# uav_controller.net
KiCad netlist of a schematic drawn in EAGLE
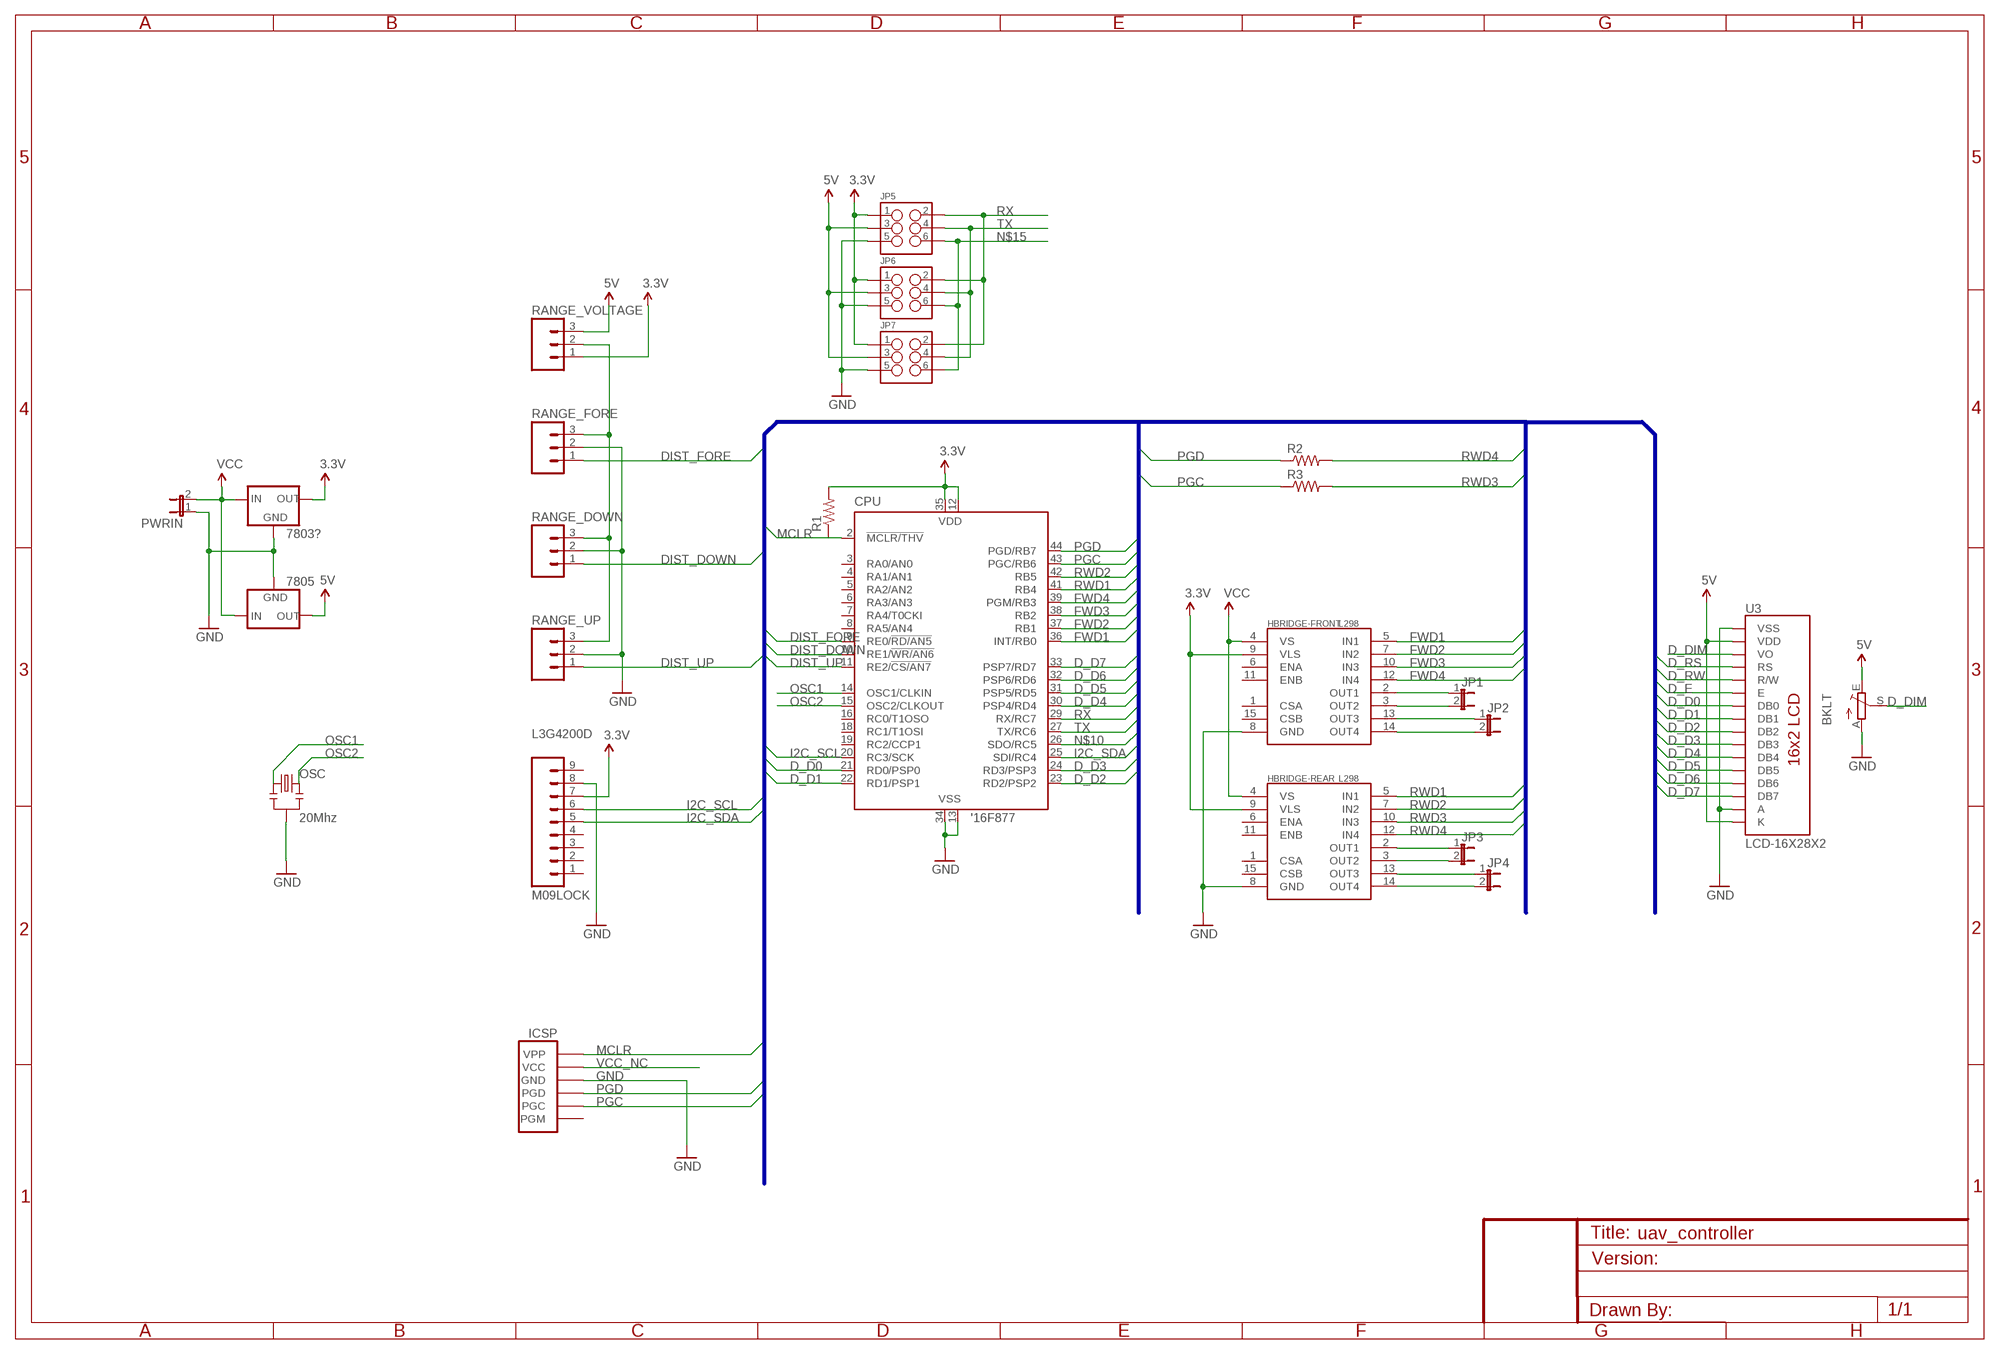
[diagram p0: schematic, sheet 1]

(export (version "E")
  (design (tool "Eeschema 10.0.6"))
  (components
    (comp (ref "7803?")
      (value "V_REG_78XX-TO-220")
      (footprint "eagle-import:TO-220-ALT")
      (libsource (lib "eagle-import") (part "V_REG_78XX-TO-220"))
    )
    (comp (ref "7805")
      (value "V_REG_78XX-TO-220")
      (footprint "eagle-import:TO-220-ALT")
      (libsource (lib "eagle-import") (part "V_REG_78XX-TO-220"))
    )
    (comp (ref "BKLT")
      (value "TRIM_EU-PT10")
      (footprint "eagle-import:PT-10")
      (libsource (lib "eagle-import") (part "TRIM_EU-PT10"))
    )
    (comp (ref "CPU")
      (value "'16F877")
      (footprint "eagle-import:S44")
      (libsource (lib "eagle-import") (part "PIC16F87SO7"))
    )
    (comp (ref "HBRIDGE-FRONT")
      (value "L298")
      (footprint "eagle-import:MULTIWATT15")
      (libsource (lib "eagle-import") (part "L298"))
    )
    (comp (ref "HBRIDGE-REAR")
      (value "L298")
      (footprint "eagle-import:MULTIWATT15")
      (libsource (lib "eagle-import") (part "L298"))
    )
    (comp (ref "ICSP")
      (value "PIC-ICSPPOLAR_LOCK")
      (footprint "eagle-import:MOLEX-1X6_LOCK")
      (libsource (lib "eagle-import") (part "PIC-ICSPPOLAR_LOCK"))
    )
    (comp (ref "JP1")
      (value "JUMPER-2PTH")
      (footprint "eagle-import:1X02")
      (libsource (lib "eagle-import") (part "JUMPER-2PTH"))
    )
    (comp (ref "JP2")
      (value "JUMPER-2PTH")
      (footprint "eagle-import:1X02")
      (libsource (lib "eagle-import") (part "JUMPER-2PTH"))
    )
    (comp (ref "JP3")
      (value "JUMPER-2PTH")
      (footprint "eagle-import:1X02")
      (libsource (lib "eagle-import") (part "JUMPER-2PTH"))
    )
    (comp (ref "JP4")
      (value "JUMPER-2PTH")
      (footprint "eagle-import:1X02")
      (libsource (lib "eagle-import") (part "JUMPER-2PTH"))
    )
    (comp (ref "JP5")
      (value "M03X2")
      (footprint "eagle-import:2X3-SHROUDED")
      (libsource (lib "eagle-import") (part "M03X2"))
    )
    (comp (ref "JP6")
      (value "M03X2")
      (footprint "eagle-import:2X3-SHROUDED")
      (libsource (lib "eagle-import") (part "M03X2"))
    )
    (comp (ref "JP7")
      (value "M03X2")
      (footprint "eagle-import:2X3-SHROUDED")
      (libsource (lib "eagle-import") (part "M03X2"))
    )
    (comp (ref "L3G4200D")
      (value "M09LOCK")
      (footprint "eagle-import:1X09_LOCK")
      (libsource (lib "eagle-import") (part "M09LOCK"))
    )
    (comp (ref "OSC")
      (value "20Mhz")
      (footprint "eagle-import:RESONATOR-PTH")
      (libsource (lib "eagle-import") (part "RESONATORPTH"))
    )
    (comp (ref "PWRIN")
      (value "JUMPER-2PTH")
      (footprint "eagle-import:1X02")
      (libsource (lib "eagle-import") (part "JUMPER-2PTH"))
    )
    (comp (ref "R1")
      (value "RESISTOREZ")
      (footprint "eagle-import:AXIAL-0.3EZ")
      (libsource (lib "eagle-import") (part "RESISTOREZ"))
    )
    (comp (ref "R2")
      (value "RESISTORKIT")
      (footprint "eagle-import:AXIAL-0.3-KIT")
      (libsource (lib "eagle-import") (part "RESISTORKIT"))
    )
    (comp (ref "R3")
      (value "RESISTORKIT")
      (footprint "eagle-import:AXIAL-0.3-KIT")
      (libsource (lib "eagle-import") (part "RESISTORKIT"))
    )
    (comp (ref "RANGE_DOWN")
      (value "M03JST-PTH")
      (footprint "eagle-import:JST-3-PTH")
      (libsource (lib "eagle-import") (part "M03JST-PTH"))
    )
    (comp (ref "RANGE_FORE")
      (value "M03JST-PTH")
      (footprint "eagle-import:JST-3-PTH")
      (libsource (lib "eagle-import") (part "M03JST-PTH"))
    )
    (comp (ref "RANGE_UP")
      (value "M03JST-PTH")
      (footprint "eagle-import:JST-3-PTH")
      (libsource (lib "eagle-import") (part "M03JST-PTH"))
    )
    (comp (ref "RANGE_VOLTAGE")
      (value "M03PTH")
      (footprint "eagle-import:1X03")
      (libsource (lib "eagle-import") (part "M03PTH"))
    )
    (comp (ref "U3")
      (value "LCD-16X28X2")
      (footprint "eagle-import:LCD-8X2")
      (libsource (lib "eagle-import") (part "LCD-16X28X2"))
    )
  )
  (nets
    (net (code "1") (name "/DIST_DOWN") (class "Default")
      (node (ref "CPU") (pin "10") (pinfunction "RE1/~{WR/AN6}_10") (pintype "bidirectional"))
      (node (ref "RANGE_DOWN") (pin "1") (pinfunction "1_1") (pintype "passive"))
    )
    (net (code "2") (name "/DIST_FORE") (class "Default")
      (node (ref "CPU") (pin "9") (pinfunction "RE0/~{RD/AN5}_9") (pintype "bidirectional"))
      (node (ref "RANGE_FORE") (pin "1") (pinfunction "1_1") (pintype "passive"))
    )
    (net (code "3") (name "/DIST_UP") (class "Default")
      (node (ref "CPU") (pin "11") (pinfunction "RE2/~{CS/AN7}_11") (pintype "bidirectional"))
      (node (ref "RANGE_UP") (pin "1") (pinfunction "1_1") (pintype "passive"))
    )
    (net (code "4") (name "/D_D0") (class "Default")
      (node (ref "CPU") (pin "21") (pinfunction "RD0/PSP0_21") (pintype "bidirectional"))
      (node (ref "U3") (pin "7") (pinfunction "DB0_7") (pintype "bidirectional"))
    )
    (net (code "5") (name "/D_D1") (class "Default")
      (node (ref "CPU") (pin "22") (pinfunction "RD1/PSP1_22") (pintype "bidirectional"))
      (node (ref "U3") (pin "8") (pinfunction "DB1_8") (pintype "bidirectional"))
    )
    (net (code "6") (name "/D_D2") (class "Default")
      (node (ref "CPU") (pin "23") (pinfunction "RD2/PSP2_23") (pintype "bidirectional"))
      (node (ref "U3") (pin "9") (pinfunction "DB2_9") (pintype "bidirectional"))
    )
    (net (code "7") (name "/D_D3") (class "Default")
      (node (ref "CPU") (pin "24") (pinfunction "RD3/PSP3_24") (pintype "bidirectional"))
      (node (ref "U3") (pin "10") (pinfunction "DB3_10") (pintype "bidirectional"))
    )
    (net (code "8") (name "/D_D4") (class "Default")
      (node (ref "CPU") (pin "30") (pinfunction "PSP4/RD4_30") (pintype "bidirectional"))
      (node (ref "U3") (pin "11") (pinfunction "DB4_11") (pintype "bidirectional"))
    )
    (net (code "9") (name "/D_D5") (class "Default")
      (node (ref "CPU") (pin "31") (pinfunction "PSP5/RD5_31") (pintype "bidirectional"))
      (node (ref "U3") (pin "12") (pinfunction "DB5_12") (pintype "bidirectional"))
    )
    (net (code "10") (name "/D_D6") (class "Default")
      (node (ref "CPU") (pin "32") (pinfunction "PSP6/RD6_32") (pintype "bidirectional"))
      (node (ref "U3") (pin "13") (pinfunction "DB6_13") (pintype "bidirectional"))
    )
    (net (code "11") (name "/D_D7") (class "Default")
      (node (ref "CPU") (pin "33") (pinfunction "PSP7/RD7_33") (pintype "bidirectional"))
      (node (ref "U3") (pin "14") (pinfunction "DB7_14") (pintype "bidirectional"))
    )
    (net (code "12") (name "/D_DIM") (class "Default")
      (node (ref "BKLT") (pin "S") (pinfunction "S_S") (pintype "passive"))
      (node (ref "U3") (pin "3") (pinfunction "VO_3") (pintype "bidirectional"))
    )
    (net (code "13") (name "/D_E") (class "Default")
      (node (ref "U3") (pin "6") (pinfunction "E_6") (pintype "input"))
    )
    (net (code "14") (name "/D_RS") (class "Default")
      (node (ref "U3") (pin "4") (pinfunction "RS_4") (pintype "input"))
    )
    (net (code "15") (name "/D_RW") (class "Default")
      (node (ref "U3") (pin "5") (pinfunction "R/W_5") (pintype "input"))
    )
    (net (code "16") (name "/FWD1") (class "Default")
      (node (ref "CPU") (pin "36") (pinfunction "INT/RB0_36") (pintype "bidirectional"))
      (node (ref "HBRIDGE-FRONT") (pin "5") (pinfunction "IN1_5") (pintype "bidirectional"))
    )
    (net (code "17") (name "/FWD2") (class "Default")
      (node (ref "CPU") (pin "37") (pinfunction "RB1_37") (pintype "bidirectional"))
      (node (ref "HBRIDGE-FRONT") (pin "7") (pinfunction "IN2_7") (pintype "bidirectional"))
    )
    (net (code "18") (name "/FWD3") (class "Default")
      (node (ref "CPU") (pin "38") (pinfunction "RB2_38") (pintype "bidirectional"))
      (node (ref "HBRIDGE-FRONT") (pin "10") (pinfunction "IN3_10") (pintype "bidirectional"))
    )
    (net (code "19") (name "/FWD4") (class "Default")
      (node (ref "CPU") (pin "39") (pinfunction "PGM/RB3_39") (pintype "bidirectional"))
      (node (ref "HBRIDGE-FRONT") (pin "12") (pinfunction "IN4_12") (pintype "bidirectional"))
    )
    (net (code "20") (name "/I2C_SCL") (class "Default")
      (node (ref "CPU") (pin "20") (pinfunction "RC3/SCK_20") (pintype "bidirectional"))
      (node (ref "L3G4200D") (pin "6") (pinfunction "6_6") (pintype "passive"))
    )
    (net (code "21") (name "/I2C_SDA") (class "Default")
      (node (ref "CPU") (pin "25") (pinfunction "SDI/RC4_25") (pintype "bidirectional"))
      (node (ref "L3G4200D") (pin "5") (pinfunction "5_5") (pintype "passive"))
    )
    (net (code "22") (name "/MCLR") (class "Default")
      (node (ref "CPU") (pin "2") (pinfunction "~{MCLR/THV}_2") (pintype "input"))
      (node (ref "ICSP") (pin "6") (pinfunction "VPP_6") (pintype "bidirectional"))
      (node (ref "R1") (pin "P$1") (pinfunction "1_P$1") (pintype "passive"))
    )
    (net (code "23") (name "/N$10") (class "Default")
      (node (ref "CPU") (pin "26") (pinfunction "SDO/RC5_26") (pintype "bidirectional"))
    )
    (net (code "24") (name "/N$15") (class "Default")
      (node (ref "JP5") (pin "6") (pinfunction "6_6") (pintype "bidirectional"))
      (node (ref "JP6") (pin "6") (pinfunction "6_6") (pintype "bidirectional"))
      (node (ref "JP7") (pin "6") (pinfunction "6_6") (pintype "bidirectional"))
    )
    (net (code "25") (name "/OSC1") (class "Default")
      (node (ref "CPU") (pin "14") (pinfunction "OSC1/CLKIN_14") (pintype "input"))
      (node (ref "OSC") (pin "1") (pinfunction "1_1") (pintype "passive"))
    )
    (net (code "26") (name "/OSC2") (class "Default")
      (node (ref "CPU") (pin "15") (pinfunction "OSC2/CLKOUT_15") (pintype "output"))
      (node (ref "OSC") (pin "3") (pinfunction "3_3") (pintype "passive"))
    )
    (net (code "27") (name "/PGC") (class "Default")
      (node (ref "CPU") (pin "43") (pinfunction "PGC/RB6_43") (pintype "bidirectional"))
      (node (ref "ICSP") (pin "2") (pinfunction "PGC_2") (pintype "bidirectional"))
      (node (ref "R3") (pin "P$1") (pinfunction "1_P$1") (pintype "passive"))
    )
    (net (code "28") (name "/PGD") (class "Default")
      (node (ref "CPU") (pin "44") (pinfunction "PGD/RB7_44") (pintype "bidirectional"))
      (node (ref "ICSP") (pin "3") (pinfunction "PGD_3") (pintype "bidirectional"))
      (node (ref "R2") (pin "P$1") (pinfunction "1_P$1") (pintype "passive"))
    )
    (net (code "29") (name "/RWD1") (class "Default")
      (node (ref "CPU") (pin "41") (pinfunction "RB4_41") (pintype "bidirectional"))
      (node (ref "HBRIDGE-REAR") (pin "5") (pinfunction "IN1_5") (pintype "bidirectional"))
    )
    (net (code "30") (name "/RWD2") (class "Default")
      (node (ref "CPU") (pin "42") (pinfunction "RB5_42") (pintype "bidirectional"))
      (node (ref "HBRIDGE-REAR") (pin "7") (pinfunction "IN2_7") (pintype "bidirectional"))
    )
    (net (code "31") (name "/RWD3") (class "Default")
      (node (ref "HBRIDGE-REAR") (pin "10") (pinfunction "IN3_10") (pintype "bidirectional"))
      (node (ref "R3") (pin "P$2") (pinfunction "2_P$2") (pintype "passive"))
    )
    (net (code "32") (name "/RWD4") (class "Default")
      (node (ref "HBRIDGE-REAR") (pin "12") (pinfunction "IN4_12") (pintype "bidirectional"))
      (node (ref "R2") (pin "P$2") (pinfunction "2_P$2") (pintype "passive"))
    )
    (net (code "33") (name "/RX") (class "Default")
      (node (ref "CPU") (pin "29") (pinfunction "RX/RC7_29") (pintype "bidirectional"))
      (node (ref "JP5") (pin "2") (pinfunction "2_2") (pintype "bidirectional"))
      (node (ref "JP6") (pin "2") (pinfunction "2_2") (pintype "bidirectional"))
      (node (ref "JP7") (pin "2") (pinfunction "2_2") (pintype "bidirectional"))
    )
    (net (code "34") (name "/TX") (class "Default")
      (node (ref "CPU") (pin "27") (pinfunction "TX/RC6_27") (pintype "bidirectional"))
      (node (ref "JP5") (pin "4") (pinfunction "4_4") (pintype "bidirectional"))
      (node (ref "JP6") (pin "4") (pinfunction "4_4") (pintype "bidirectional"))
      (node (ref "JP7") (pin "4") (pinfunction "4_4") (pintype "bidirectional"))
    )
    (net (code "35") (name "/VCC_NC") (class "Default")
      (node (ref "ICSP") (pin "5") (pinfunction "VCC_5") (pintype "bidirectional"))
    )
    (net (code "36") (name "3.3V") (class "Default")
      (node (ref "7803?") (pin "OUT") (pinfunction "OUT_OUT") (pintype "output"))
      (node (ref "CPU") (pin "12") (pinfunction "VDD_12") (pintype "power_in"))
      (node (ref "CPU") (pin "35") (pinfunction "VDD_35") (pintype "power_in"))
      (node (ref "HBRIDGE-FRONT") (pin "9") (pinfunction "VLS_9") (pintype "bidirectional"))
      (node (ref "HBRIDGE-REAR") (pin "9") (pinfunction "VLS_9") (pintype "bidirectional"))
      (node (ref "JP5") (pin "1") (pinfunction "1_1") (pintype "bidirectional"))
      (node (ref "JP6") (pin "1") (pinfunction "1_1") (pintype "bidirectional"))
      (node (ref "JP7") (pin "1") (pinfunction "1_1") (pintype "bidirectional"))
      (node (ref "L3G4200D") (pin "7") (pinfunction "7_7") (pintype "passive"))
      (node (ref "R1") (pin "P$2") (pinfunction "2_P$2") (pintype "passive"))
      (node (ref "RANGE_VOLTAGE") (pin "1") (pinfunction "1_1") (pintype "passive"))
    )
    (net (code "37") (name "5V") (class "Default")
      (node (ref "7805") (pin "OUT") (pinfunction "OUT_OUT") (pintype "output"))
      (node (ref "BKLT") (pin "E") (pinfunction "E_E") (pintype "passive"))
      (node (ref "JP5") (pin "3") (pinfunction "3_3") (pintype "bidirectional"))
      (node (ref "JP6") (pin "3") (pinfunction "3_3") (pintype "bidirectional"))
      (node (ref "JP7") (pin "3") (pinfunction "3_3") (pintype "bidirectional"))
      (node (ref "RANGE_VOLTAGE") (pin "3") (pinfunction "3_3") (pintype "passive"))
      (node (ref "U3") (pin "16") (pinfunction "K_16") (pintype "power_in"))
      (node (ref "U3") (pin "2") (pinfunction "VDD_2") (pintype "power_in"))
    )
    (net (code "38") (name "GND") (class "Default")
      (node (ref "7803?") (pin "GND") (pinfunction "GND_GND") (pintype "input"))
      (node (ref "7805") (pin "GND") (pinfunction "GND_GND") (pintype "input"))
      (node (ref "BKLT") (pin "A") (pinfunction "A_A") (pintype "passive"))
      (node (ref "CPU") (pin "13") (pinfunction "VSS_13") (pintype "power_in"))
      (node (ref "CPU") (pin "34") (pinfunction "VSS_34") (pintype "power_in"))
      (node (ref "HBRIDGE-FRONT") (pin "8") (pinfunction "GND_8") (pintype "bidirectional"))
      (node (ref "HBRIDGE-REAR") (pin "8") (pinfunction "GND_8") (pintype "bidirectional"))
      (node (ref "ICSP") (pin "4") (pinfunction "GND_4") (pintype "bidirectional"))
      (node (ref "JP5") (pin "5") (pinfunction "5_5") (pintype "bidirectional"))
      (node (ref "JP6") (pin "5") (pinfunction "5_5") (pintype "bidirectional"))
      (node (ref "JP7") (pin "5") (pinfunction "5_5") (pintype "bidirectional"))
      (node (ref "L3G4200D") (pin "8") (pinfunction "8_8") (pintype "passive"))
      (node (ref "OSC") (pin "2") (pinfunction "2_2") (pintype "passive"))
      (node (ref "PWRIN") (pin "1") (pinfunction "1_1") (pintype "passive"))
      (node (ref "RANGE_DOWN") (pin "2") (pinfunction "2_2") (pintype "passive"))
      (node (ref "RANGE_FORE") (pin "2") (pinfunction "2_2") (pintype "passive"))
      (node (ref "RANGE_UP") (pin "2") (pinfunction "2_2") (pintype "passive"))
      (node (ref "U3") (pin "1") (pinfunction "VSS_1") (pintype "power_in"))
      (node (ref "U3") (pin "15") (pinfunction "A_15") (pintype "power_in"))
    )
    (net (code "39") (name "Net-(HBRIDGE-FRONT-OUT1)") (class "Default")
      (node (ref "HBRIDGE-FRONT") (pin "2") (pinfunction "OUT1_2") (pintype "bidirectional"))
      (node (ref "JP1") (pin "1") (pinfunction "1_1") (pintype "passive"))
    )
    (net (code "40") (name "Net-(HBRIDGE-FRONT-OUT2)") (class "Default")
      (node (ref "HBRIDGE-FRONT") (pin "3") (pinfunction "OUT2_3") (pintype "bidirectional"))
      (node (ref "JP1") (pin "2") (pinfunction "2_2") (pintype "passive"))
    )
    (net (code "41") (name "Net-(HBRIDGE-FRONT-OUT3)") (class "Default")
      (node (ref "HBRIDGE-FRONT") (pin "13") (pinfunction "OUT3_13") (pintype "bidirectional"))
      (node (ref "JP2") (pin "1") (pinfunction "1_1") (pintype "passive"))
    )
    (net (code "42") (name "Net-(HBRIDGE-FRONT-OUT4)") (class "Default")
      (node (ref "HBRIDGE-FRONT") (pin "14") (pinfunction "OUT4_14") (pintype "bidirectional"))
      (node (ref "JP2") (pin "2") (pinfunction "2_2") (pintype "passive"))
    )
    (net (code "43") (name "Net-(HBRIDGE-REAR-OUT1)") (class "Default")
      (node (ref "HBRIDGE-REAR") (pin "2") (pinfunction "OUT1_2") (pintype "bidirectional"))
      (node (ref "JP3") (pin "1") (pinfunction "1_1") (pintype "passive"))
    )
    (net (code "44") (name "Net-(HBRIDGE-REAR-OUT2)") (class "Default")
      (node (ref "HBRIDGE-REAR") (pin "3") (pinfunction "OUT2_3") (pintype "bidirectional"))
      (node (ref "JP3") (pin "2") (pinfunction "2_2") (pintype "passive"))
    )
    (net (code "45") (name "Net-(HBRIDGE-REAR-OUT3)") (class "Default")
      (node (ref "HBRIDGE-REAR") (pin "13") (pinfunction "OUT3_13") (pintype "bidirectional"))
      (node (ref "JP4") (pin "1") (pinfunction "1_1") (pintype "passive"))
    )
    (net (code "46") (name "Net-(HBRIDGE-REAR-OUT4)") (class "Default")
      (node (ref "HBRIDGE-REAR") (pin "14") (pinfunction "OUT4_14") (pintype "bidirectional"))
      (node (ref "JP4") (pin "2") (pinfunction "2_2") (pintype "passive"))
    )
    (net (code "47") (name "Net-(RANGE_DOWN-Pad3)") (class "Default")
      (node (ref "RANGE_DOWN") (pin "3") (pinfunction "3_3") (pintype "passive"))
      (node (ref "RANGE_FORE") (pin "3") (pinfunction "3_3") (pintype "passive"))
      (node (ref "RANGE_UP") (pin "3") (pinfunction "3_3") (pintype "passive"))
      (node (ref "RANGE_VOLTAGE") (pin "2") (pinfunction "2_2") (pintype "passive"))
    )
    (net (code "48") (name "VCC") (class "Default")
      (node (ref "7803?") (pin "IN") (pinfunction "IN_IN") (pintype "input"))
      (node (ref "7805") (pin "IN") (pinfunction "IN_IN") (pintype "input"))
      (node (ref "HBRIDGE-FRONT") (pin "4") (pinfunction "VS_4") (pintype "bidirectional"))
      (node (ref "HBRIDGE-REAR") (pin "4") (pinfunction "VS_4") (pintype "bidirectional"))
      (node (ref "PWRIN") (pin "2") (pinfunction "2_2") (pintype "passive"))
    )
    (net (code "49") (name "unconnected-(CPU-RA0{slash}AN0-Pad3)") (class "Default")
      (node (ref "CPU") (pin "3") (pinfunction "RA0/AN0_3") (pintype "bidirectional"))
    )
    (net (code "50") (name "unconnected-(CPU-RA1{slash}AN1-Pad4)") (class "Default")
      (node (ref "CPU") (pin "4") (pinfunction "RA1/AN1_4") (pintype "bidirectional"))
    )
    (net (code "51") (name "unconnected-(CPU-RA2{slash}AN2-Pad5)") (class "Default")
      (node (ref "CPU") (pin "5") (pinfunction "RA2/AN2_5") (pintype "bidirectional"))
    )
    (net (code "52") (name "unconnected-(CPU-RA3{slash}AN3-Pad6)") (class "Default")
      (node (ref "CPU") (pin "6") (pinfunction "RA3/AN3_6") (pintype "bidirectional"))
    )
    (net (code "53") (name "unconnected-(CPU-RA4{slash}T0CKI-Pad7)") (class "Default")
      (node (ref "CPU") (pin "7") (pinfunction "RA4/T0CKI_7") (pintype "bidirectional"))
    )
    (net (code "54") (name "unconnected-(CPU-RA5{slash}AN4-Pad8)") (class "Default")
      (node (ref "CPU") (pin "8") (pinfunction "RA5/AN4_8") (pintype "bidirectional"))
    )
    (net (code "55") (name "unconnected-(CPU-RC0{slash}T1OSO-Pad16)") (class "Default")
      (node (ref "CPU") (pin "16") (pinfunction "RC0/T1OSO_16") (pintype "bidirectional"))
    )
    (net (code "56") (name "unconnected-(CPU-RC1{slash}T1OSI-Pad18)") (class "Default")
      (node (ref "CPU") (pin "18") (pinfunction "RC1/T1OSI_18") (pintype "bidirectional"))
    )
    (net (code "57") (name "unconnected-(CPU-RC2{slash}CCP1-Pad19)") (class "Default")
      (node (ref "CPU") (pin "19") (pinfunction "RC2/CCP1_19") (pintype "bidirectional"))
    )
    (net (code "58") (name "unconnected-(HBRIDGE-FRONT-CSA-Pad1)") (class "Default")
      (node (ref "HBRIDGE-FRONT") (pin "1") (pinfunction "CSA_1") (pintype "bidirectional"))
    )
    (net (code "59") (name "unconnected-(HBRIDGE-FRONT-CSB-Pad15)") (class "Default")
      (node (ref "HBRIDGE-FRONT") (pin "15") (pinfunction "CSB_15") (pintype "bidirectional"))
    )
    (net (code "60") (name "unconnected-(HBRIDGE-FRONT-ENA-Pad6)") (class "Default")
      (node (ref "HBRIDGE-FRONT") (pin "6") (pinfunction "ENA_6") (pintype "bidirectional"))
    )
    (net (code "61") (name "unconnected-(HBRIDGE-FRONT-ENB-Pad11)") (class "Default")
      (node (ref "HBRIDGE-FRONT") (pin "11") (pinfunction "ENB_11") (pintype "bidirectional"))
    )
    (net (code "62") (name "unconnected-(HBRIDGE-REAR-CSA-Pad1)") (class "Default")
      (node (ref "HBRIDGE-REAR") (pin "1") (pinfunction "CSA_1") (pintype "bidirectional"))
    )
    (net (code "63") (name "unconnected-(HBRIDGE-REAR-CSB-Pad15)") (class "Default")
      (node (ref "HBRIDGE-REAR") (pin "15") (pinfunction "CSB_15") (pintype "bidirectional"))
    )
    (net (code "64") (name "unconnected-(HBRIDGE-REAR-ENA-Pad6)") (class "Default")
      (node (ref "HBRIDGE-REAR") (pin "6") (pinfunction "ENA_6") (pintype "bidirectional"))
    )
    (net (code "65") (name "unconnected-(HBRIDGE-REAR-ENB-Pad11)") (class "Default")
      (node (ref "HBRIDGE-REAR") (pin "11") (pinfunction "ENB_11") (pintype "bidirectional"))
    )
    (net (code "66") (name "unconnected-(ICSP-PGM-Pad1)") (class "Default")
      (node (ref "ICSP") (pin "1") (pinfunction "PGM_1") (pintype "bidirectional"))
    )
    (net (code "67") (name "unconnected-(L3G4200D-Pad1)") (class "Default")
      (node (ref "L3G4200D") (pin "1") (pinfunction "1_1") (pintype "passive"))
    )
    (net (code "68") (name "unconnected-(L3G4200D-Pad2)") (class "Default")
      (node (ref "L3G4200D") (pin "2") (pinfunction "2_2") (pintype "passive"))
    )
    (net (code "69") (name "unconnected-(L3G4200D-Pad3)") (class "Default")
      (node (ref "L3G4200D") (pin "3") (pinfunction "3_3") (pintype "passive"))
    )
    (net (code "70") (name "unconnected-(L3G4200D-Pad4)") (class "Default")
      (node (ref "L3G4200D") (pin "4") (pinfunction "4_4") (pintype "passive"))
    )
    (net (code "71") (name "unconnected-(L3G4200D-Pad9)") (class "Default")
      (node (ref "L3G4200D") (pin "9") (pinfunction "9_9") (pintype "passive"))
    )
  )
)
